# RK3562-VCCIO5.net
KiCad netlist of a schematic drawn in Altium Designer
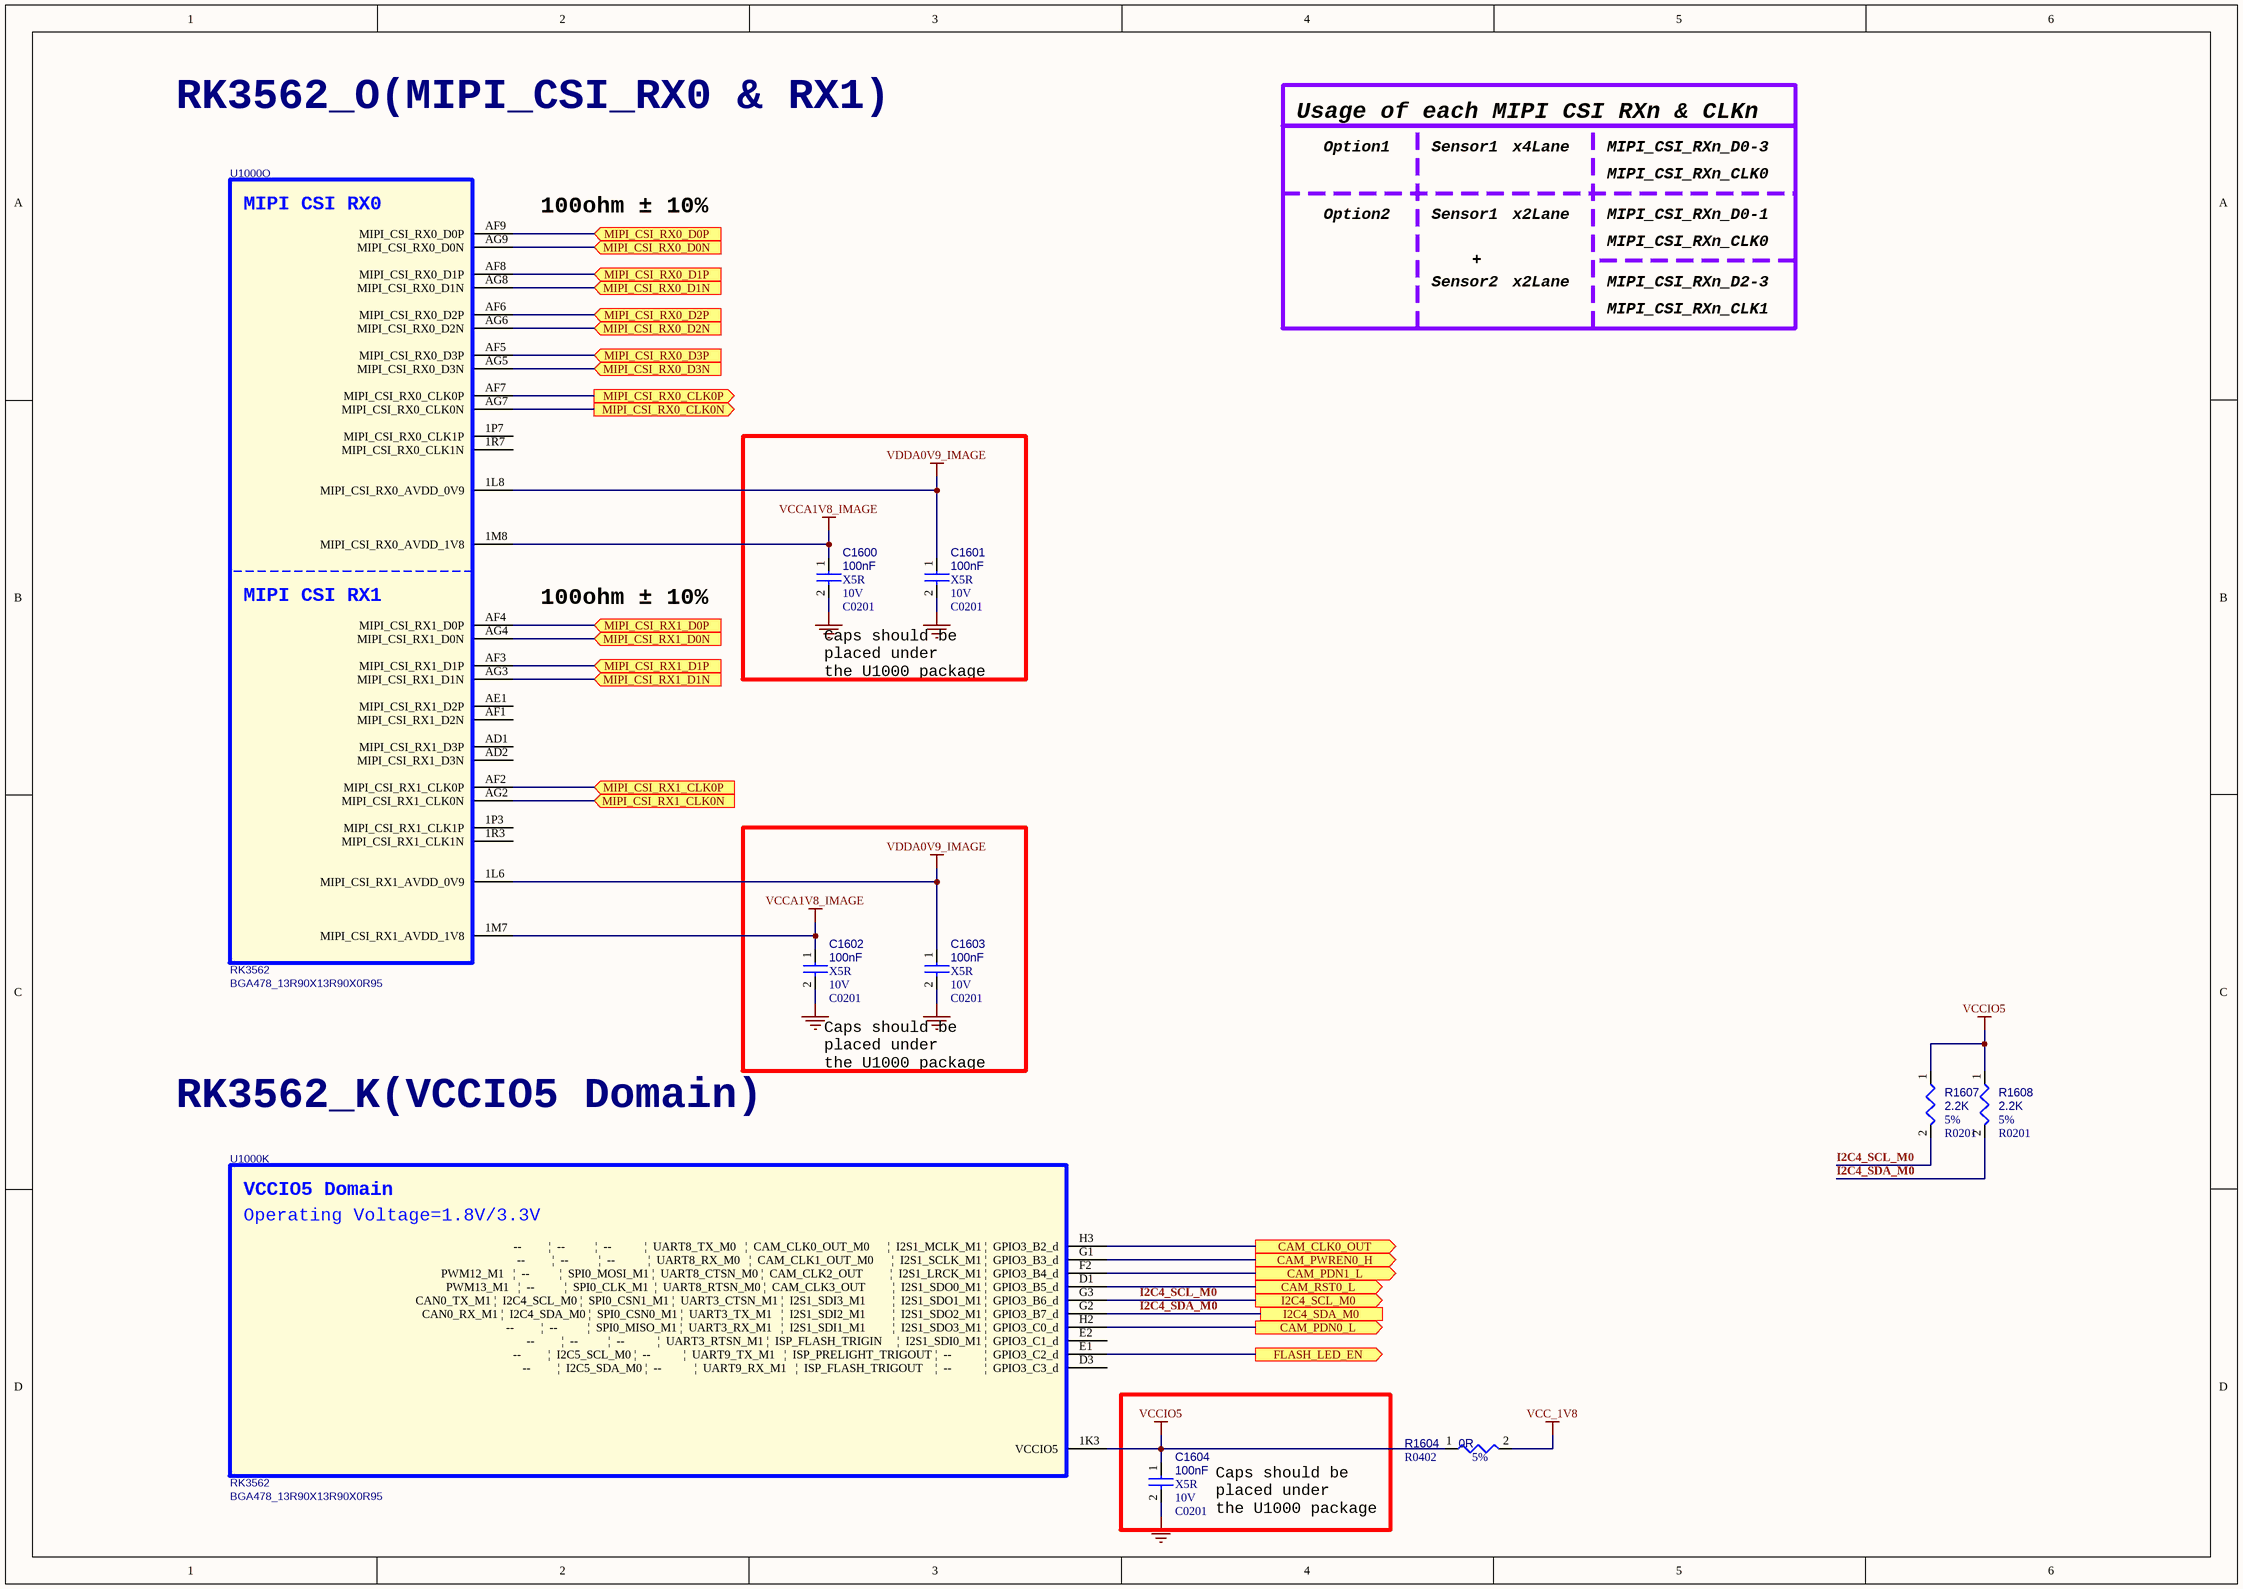
[diagram p0: RK3562-VCCIO5.SchDoc]

(export (version "E")
  (design (tool "Eeschema 10.0.6"))
  (components
    (comp (ref "C1600")
      (value "100nF")
      (footprint "C0201")
      (description "cap,100.00nF,+/-10%,10V,X5R,C0201")
      (fields
        (field (name "DIELECTRIC") "X5R")
        (field (name "PCB FOOTPRINT") "C0201")
        (field (name "VOLTAGE") "10V")
        (field (name "TOLERANCE") "10%")
        (field (name "MANUFACTURER") "TDK")
        (field (name "CREATED BY") "JJJ")
      )
      (libsource (lib "RK3562_REF") (part "CAP NP"))
    )
    (comp (ref "C1601")
      (value "100nF")
      (footprint "C0201")
      (description "cap,100.00nF,+/-10%,10V,X5R,C0201")
      (fields
        (field (name "DIELECTRIC") "X5R")
        (field (name "PCB FOOTPRINT") "C0201")
        (field (name "VOLTAGE") "10V")
        (field (name "MANUFACTURER") "TDK")
        (field (name "TOLERANCE") "10%")
        (field (name "CREATED BY") "JJJ")
      )
      (libsource (lib "RK3562_REF") (part "CAP NP"))
    )
    (comp (ref "C1602")
      (value "100nF")
      (footprint "C0201")
      (description "cap,100.00nF,+/-10%,10V,X5R,C0201")
      (fields
        (field (name "DIELECTRIC") "X5R")
        (field (name "PCB FOOTPRINT") "C0201")
        (field (name "VOLTAGE") "10V")
        (field (name "TOLERANCE") "10%")
        (field (name "MANUFACTURER") "TDK")
        (field (name "CREATED BY") "JJJ")
      )
      (libsource (lib "RK3562_REF") (part "CAP NP"))
    )
    (comp (ref "C1603")
      (value "100nF")
      (footprint "C0201")
      (description "cap,100.00nF,+/-10%,10V,X5R,C0201")
      (fields
        (field (name "DIELECTRIC") "X5R")
        (field (name "PCB FOOTPRINT") "C0201")
        (field (name "VOLTAGE") "10V")
        (field (name "MANUFACTURER") "TDK")
        (field (name "TOLERANCE") "10%")
        (field (name "CREATED BY") "JJJ")
      )
      (libsource (lib "RK3562_REF") (part "CAP NP"))
    )
    (comp (ref "C1604")
      (value "100nF")
      (footprint "C0201")
      (description "cap,100.00nF,+/-10%,10V,X5R,C0201")
      (fields
        (field (name "DIELECTRIC") "X5R")
        (field (name "PCB FOOTPRINT") "C0201")
        (field (name "VOLTAGE") "10V")
        (field (name "TOLERANCE") "10%")
        (field (name "MANUFACTURER") "TDK")
        (field (name "CREATED BY") "JJJ")
      )
      (libsource (lib "RK3562_REF") (part "CAP NP"))
    )
    (comp (ref "R1604")
      (value "0R")
      (footprint "R0402")
      (description "通用厚膜电阻,0R,+/-5%,R0402,1/16W.")
      (fields
        (field (name "TOLERANCE") "5%")
        (field (name "PCB FOOTPRINT") "R0402")
        (field (name "MANUFACTURER") "YAGEO")
        (field (name "CREATED BY") "YTL")
      )
      (libsource (lib "RK3562_REF") (part "RESISTOR"))
    )
    (comp (ref "R1607")
      (value "2.2K")
      (footprint "R0201")
      (description "通用厚膜电阻,2K2,+/-5%,R0201,1/20W.")
      (fields
        (field (name "TOLERANCE") "5%")
        (field (name "PCB FOOTPRINT") "R0201")
        (field (name "MANUFACTURER") "YAGEO")
        (field (name "CREATED BY") "YTL")
      )
      (libsource (lib "RK3562_REF") (part "RESISTOR"))
    )
    (comp (ref "R1608")
      (value "2.2K")
      (footprint "R0201")
      (description "通用厚膜电阻,2K2,+/-5%,R0201,1/20W.")
      (fields
        (field (name "TOLERANCE") "5%")
        (field (name "PCB FOOTPRINT") "R0201")
        (field (name "MANUFACTURER") "YAGEO")
        (field (name "CREATED BY") "YTL")
      )
      (libsource (lib "RK3562_REF") (part "RESISTOR"))
    )
    (comp (ref "U1000")
      (value "RK3562")
      (footprint "BGA478_13R90X13R90X0R95")
      (description "ROCKCHIP SOC")
      (fields
        (field (name "PCB FOOTPRINT") "BGA478_13R90X13R90X0R95")
        (field (name "MANUFACTURER") "Rockchip (瑞芯微)")
        (field (name "CREATED BY") "JJJ")
      )
      (libsource (lib "RK3562_REF") (part "SOC_RK3562"))
    )
  )
  (nets
    (net (code "1") (name "/CAM_CLK0_OUT") (class "Default")
      (node (ref "U1000") (pin "H3") (pinfunction "--_________¦__--__________¦__--___________¦__UART8_TX_M0___¦__CAM_CLK0_OUT_M0______¦__I2S1_MCLK_M1_¦__GPIO3_B2_d_H3") (pintype "passive"))
    )
    (net (code "2") (name "/CAM_PDN0_L") (class "Default")
      (node (ref "U1000") (pin "H2") (pinfunction "--_________¦__--__________¦__SPI0_MISO_M1_¦__UART3_RX_M1___¦__I2S1_SDI1_M1_________¦__I2S1_SDO3_M1_¦__GPIO3_C0_d_H2") (pintype "passive"))
    )
    (net (code "3") (name "/CAM_PDN1_L") (class "Default")
      (node (ref "U1000") (pin "F2") (pinfunction "PWM12_M1___¦__--__________¦__SPI0_MOSI_M1_¦__UART8_CTSN_M0_¦__CAM_CLK2_OUT_________¦__I2S1_LRCK_M1_¦__GPIO3_B4_d_F2") (pintype "passive"))
    )
    (net (code "4") (name "/CAM_PWREN0_H") (class "Default")
      (node (ref "U1000") (pin "G1") (pinfunction "--_________¦__--__________¦__--___________¦__UART8_RX_M0___¦__CAM_CLK1_OUT_M0______¦__I2S1_SCLK_M1_¦__GPIO3_B3_d_G1") (pintype "passive"))
    )
    (net (code "5") (name "/CAM_RST0_L") (class "Default")
      (node (ref "U1000") (pin "D1") (pinfunction "PWM13_M1___¦__--__________¦__SPI0_CLK_M1__¦__UART8_RTSN_M0_¦__CAM_CLK3_OUT_________¦__I2S1_SDO0_M1_¦__GPIO3_B5_d_D1") (pintype "passive"))
    )
    (net (code "6") (name "/FLASH_LED_EN") (class "Default")
      (node (ref "U1000") (pin "E1") (pinfunction "--_________¦__I2C5_SCL_M0_¦__--___________¦__UART9_TX_M1___¦__ISP_PRELIGHT_TRIGOUT_¦__--___________¦__GPIO3_C2_d_E1") (pintype "passive"))
    )
    (net (code "7") (name "/I2C4_SCL_M0") (class "Default")
      (node (ref "R1607") (pin "2") (pinfunction "2_2") (pintype "passive"))
      (node (ref "U1000") (pin "G3") (pinfunction "CAN0_TX_M1_¦__I2C4_SCL_M0_¦__SPI0_CSN1_M1_¦__UART3_CTSN_M1_¦__I2S1_SDI3_M1_________¦__I2S1_SDO1_M1_¦__GPIO3_B6_d_G3") (pintype "passive"))
    )
    (net (code "8") (name "/I2C4_SDA_M0") (class "Default")
      (node (ref "R1608") (pin "2") (pinfunction "2_2") (pintype "passive"))
      (node (ref "U1000") (pin "G2") (pinfunction "CAN0_RX_M1_¦__I2C4_SDA_M0_¦__SPI0_CSN0_M1_¦__UART3_TX_M1___¦__I2S1_SDI2_M1_________¦__I2S1_SDO2_M1_¦__GPIO3_B7_d_G2") (pintype "passive"))
    )
    (net (code "9") (name "/MIPI_CSI_RX0_CLK0N") (class "Default")
      (node (ref "U1000") (pin "AG7") (pinfunction "MIPI_CSI_RX0_CLK0N_AG7") (pintype "passive"))
    )
    (net (code "10") (name "/MIPI_CSI_RX0_CLK0P") (class "Default")
      (node (ref "U1000") (pin "AF7") (pinfunction "MIPI_CSI_RX0_CLK0P_AF7") (pintype "passive"))
    )
    (net (code "11") (name "/MIPI_CSI_RX0_D0N") (class "Default")
      (node (ref "U1000") (pin "AG9") (pinfunction "MIPI_CSI_RX0_D0N_AG9") (pintype "passive"))
    )
    (net (code "12") (name "/MIPI_CSI_RX0_D0P") (class "Default")
      (node (ref "U1000") (pin "AF9") (pinfunction "MIPI_CSI_RX0_D0P_AF9") (pintype "passive"))
    )
    (net (code "13") (name "/MIPI_CSI_RX0_D1N") (class "Default")
      (node (ref "U1000") (pin "AG8") (pinfunction "MIPI_CSI_RX0_D1N_AG8") (pintype "passive"))
    )
    (net (code "14") (name "/MIPI_CSI_RX0_D1P") (class "Default")
      (node (ref "U1000") (pin "AF8") (pinfunction "MIPI_CSI_RX0_D1P_AF8") (pintype "passive"))
    )
    (net (code "15") (name "/MIPI_CSI_RX0_D2N") (class "Default")
      (node (ref "U1000") (pin "AG6") (pinfunction "MIPI_CSI_RX0_D2N_AG6") (pintype "passive"))
    )
    (net (code "16") (name "/MIPI_CSI_RX0_D2P") (class "Default")
      (node (ref "U1000") (pin "AF6") (pinfunction "MIPI_CSI_RX0_D2P_AF6") (pintype "passive"))
    )
    (net (code "17") (name "/MIPI_CSI_RX0_D3N") (class "Default")
      (node (ref "U1000") (pin "AG5") (pinfunction "MIPI_CSI_RX0_D3N_AG5") (pintype "passive"))
    )
    (net (code "18") (name "/MIPI_CSI_RX0_D3P") (class "Default")
      (node (ref "U1000") (pin "AF5") (pinfunction "MIPI_CSI_RX0_D3P_AF5") (pintype "passive"))
    )
    (net (code "19") (name "/MIPI_CSI_RX1_CLK0N") (class "Default")
      (node (ref "U1000") (pin "AG2") (pinfunction "MIPI_CSI_RX1_CLK0N_AG2") (pintype "passive"))
    )
    (net (code "20") (name "/MIPI_CSI_RX1_CLK0P") (class "Default")
      (node (ref "U1000") (pin "AF2") (pinfunction "MIPI_CSI_RX1_CLK0P_AF2") (pintype "passive"))
    )
    (net (code "21") (name "/MIPI_CSI_RX1_D0N") (class "Default")
      (node (ref "U1000") (pin "AG4") (pinfunction "MIPI_CSI_RX1_D0N_AG4") (pintype "passive"))
    )
    (net (code "22") (name "/MIPI_CSI_RX1_D0P") (class "Default")
      (node (ref "U1000") (pin "AF4") (pinfunction "MIPI_CSI_RX1_D0P_AF4") (pintype "passive"))
    )
    (net (code "23") (name "/MIPI_CSI_RX1_D1N") (class "Default")
      (node (ref "U1000") (pin "AG3") (pinfunction "MIPI_CSI_RX1_D1N_AG3") (pintype "passive"))
    )
    (net (code "24") (name "/MIPI_CSI_RX1_D1P") (class "Default")
      (node (ref "U1000") (pin "AF3") (pinfunction "MIPI_CSI_RX1_D1P_AF3") (pintype "passive"))
    )
    (net (code "25") (name "GND") (class "Default")
      (node (ref "C1600") (pin "2") (pinfunction "2_2") (pintype "passive"))
      (node (ref "C1601") (pin "2") (pinfunction "2_2") (pintype "passive"))
      (node (ref "C1602") (pin "2") (pinfunction "2_2") (pintype "passive"))
      (node (ref "C1603") (pin "2") (pinfunction "2_2") (pintype "passive"))
      (node (ref "C1604") (pin "2") (pinfunction "2_2") (pintype "passive"))
    )
    (net (code "26") (name "VCCA1V8_IMAGE") (class "Default")
      (node (ref "C1600") (pin "1") (pinfunction "1_1") (pintype "passive"))
      (node (ref "C1602") (pin "1") (pinfunction "1_1") (pintype "passive"))
      (node (ref "U1000") (pin "1M7") (pinfunction "MIPI_CSI_RX1_AVDD_1V8_1M7") (pintype "passive"))
      (node (ref "U1000") (pin "1M8") (pinfunction "MIPI_CSI_RX0_AVDD_1V8_1M8") (pintype "passive"))
    )
    (net (code "27") (name "VCCIO5") (class "Default")
      (node (ref "C1604") (pin "1") (pinfunction "1_1") (pintype "passive"))
      (node (ref "R1604") (pin "1") (pinfunction "1_1") (pintype "passive"))
      (node (ref "R1607") (pin "1") (pinfunction "1_1") (pintype "passive"))
      (node (ref "R1608") (pin "1") (pinfunction "1_1") (pintype "passive"))
      (node (ref "U1000") (pin "1K3") (pinfunction "VCCIO5_1K3") (pintype "passive"))
    )
    (net (code "28") (name "VCC_1V8") (class "Default")
      (node (ref "R1604") (pin "2") (pinfunction "2_2") (pintype "passive"))
    )
    (net (code "29") (name "VDDA0V9_IMAGE") (class "Default")
      (node (ref "C1601") (pin "1") (pinfunction "1_1") (pintype "passive"))
      (node (ref "C1603") (pin "1") (pinfunction "1_1") (pintype "passive"))
      (node (ref "U1000") (pin "1L6") (pinfunction "MIPI_CSI_RX1_AVDD_0V9_1L6") (pintype "passive"))
      (node (ref "U1000") (pin "1L8") (pinfunction "MIPI_CSI_RX0_AVDD_0V9_1L8") (pintype "passive"))
    )
    (net (code "30") (name "unconnected-(U1000K---_________¦__--__________¦__--___________¦__UART3_RTSN_M1_¦__ISP_FLASH_TRIGIN_____¦__I2S1_SDI0_M1_¦__GPIO3_C1_d-PadE2)") (class "Default")
      (node (ref "U1000") (pin "E2") (pinfunction "--_________¦__--__________¦__--___________¦__UART3_RTSN_M1_¦__ISP_FLASH_TRIGIN_____¦__I2S1_SDI0_M1_¦__GPIO3_C1_d_E2") (pintype "passive"))
    )
    (net (code "31") (name "unconnected-(U1000K---_________¦__I2C5_SDA_M0_¦__--___________¦__UART9_RX_M1___¦__ISP_FLASH_TRIGOUT____¦__--___________¦__GPIO3_C3_d-PadD3)") (class "Default")
      (node (ref "U1000") (pin "D3") (pinfunction "--_________¦__I2C5_SDA_M0_¦__--___________¦__UART9_RX_M1___¦__ISP_FLASH_TRIGOUT____¦__--___________¦__GPIO3_C3_d_D3") (pintype "passive"))
    )
    (net (code "32") (name "unconnected-(U1000O-MIPI_CSI_RX0_CLK1N-Pad1R7)") (class "Default")
      (node (ref "U1000") (pin "1R7") (pinfunction "MIPI_CSI_RX0_CLK1N_1R7") (pintype "passive"))
    )
    (net (code "33") (name "unconnected-(U1000O-MIPI_CSI_RX0_CLK1P-Pad1P7)") (class "Default")
      (node (ref "U1000") (pin "1P7") (pinfunction "MIPI_CSI_RX0_CLK1P_1P7") (pintype "passive"))
    )
    (net (code "34") (name "unconnected-(U1000O-MIPI_CSI_RX1_CLK1N-Pad1R3)") (class "Default")
      (node (ref "U1000") (pin "1R3") (pinfunction "MIPI_CSI_RX1_CLK1N_1R3") (pintype "passive"))
    )
    (net (code "35") (name "unconnected-(U1000O-MIPI_CSI_RX1_CLK1P-Pad1P3)") (class "Default")
      (node (ref "U1000") (pin "1P3") (pinfunction "MIPI_CSI_RX1_CLK1P_1P3") (pintype "passive"))
    )
    (net (code "36") (name "unconnected-(U1000O-MIPI_CSI_RX1_D2N-PadAF1)") (class "Default")
      (node (ref "U1000") (pin "AF1") (pinfunction "MIPI_CSI_RX1_D2N_AF1") (pintype "passive"))
    )
    (net (code "37") (name "unconnected-(U1000O-MIPI_CSI_RX1_D2P-PadAE1)") (class "Default")
      (node (ref "U1000") (pin "AE1") (pinfunction "MIPI_CSI_RX1_D2P_AE1") (pintype "passive"))
    )
    (net (code "38") (name "unconnected-(U1000O-MIPI_CSI_RX1_D3N-PadAD2)") (class "Default")
      (node (ref "U1000") (pin "AD2") (pinfunction "MIPI_CSI_RX1_D3N_AD2") (pintype "passive"))
    )
    (net (code "39") (name "unconnected-(U1000O-MIPI_CSI_RX1_D3P-PadAD1)") (class "Default")
      (node (ref "U1000") (pin "AD1") (pinfunction "MIPI_CSI_RX1_D3P_AD1") (pintype "passive"))
    )
  )
)
